# Sheet1.net
KiCad netlist of a schematic drawn in Altium Designer
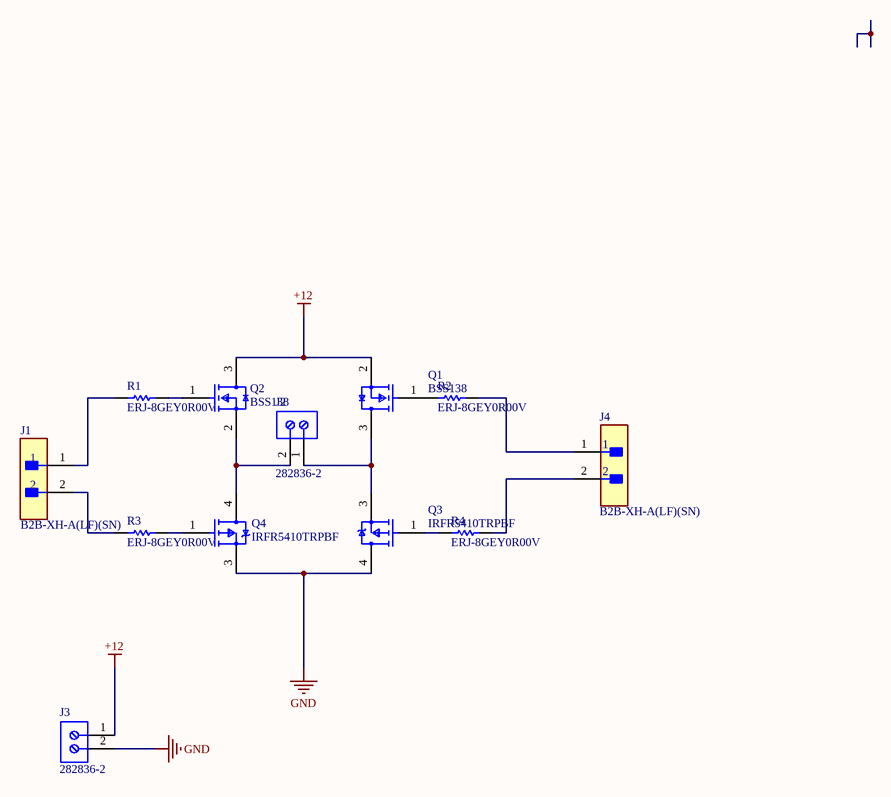
[diagram p0: Sheet1.SchDoc]

(export (version "E")
  (design (tool "Eeschema 10.0.6"))
  (components
    (comp (ref "J1")
      (value "B2B-XH-A(LF)(SN)")
      (footprint "FP-B2B-XH-A_LF_SN-MFG")
      (description "CONN HEADER VERT 2POS 2.5MM")
      (libsource (lib "") (part "3bc925449376181038e59eaffc5286c_1"))
    )
    (comp (ref "J2")
      (value "282836-2")
      (footprint "TECO-282836-2_V")
      (description "Female Header, Pitch 5 mm, 1 x 2 Position, Height 10 mm, Tail Length 3.5 mm, Rohs, Bulk")
      (fields (field (name "VOLTAGE") "300V") (field (name "MANUFACTURER") "TE Connectivity"))
      (libsource (lib "Altium Content Vault") (part "CN-1P-F-TB2"))
    )
    (comp (ref "J3")
      (value "282836-2")
      (footprint "TECO-282836-2_V")
      (description "Female Header, Pitch 5 mm, 1 x 2 Position, Height 10 mm, Tail Length 3.5 mm, Rohs, Bulk")
      (fields (field (name "VOLTAGE") "300V") (field (name "MANUFACTURER") "TE Connectivity"))
      (libsource (lib "Altium Content Vault") (part "CN-1P-F-TB2"))
    )
    (comp (ref "J4")
      (value "B2B-XH-A(LF)(SN)")
      (footprint "FP-B2B-XH-A_LF_SN-MFG")
      (description "CONN HEADER VERT 2POS 2.5MM")
      (libsource (lib "Altium Content Vault") (part "3bc925449376181038e59eaffc5286c"))
    )
    (comp (ref "Q1")
      (value "BSS138")
      (footprint "FP-318-08-IPC_B")
      (description "MOSFET N-CH 50V 220MA SOT-23")
      (libsource (lib "Altium Content Vault") (part "3b9c635fedb024a5347a57b145af9cc"))
    )
    (comp (ref "Q2")
      (value "BSS138")
      (footprint "FP-318-08-IPC_B")
      (description "MOSFET N-CH 50V 220MA SOT-23")
      (libsource (lib "Altium Content Vault") (part "3b9c635fedb024a5347a57b145af9cc"))
    )
    (comp (ref "Q3")
      (value "IRFR5410TRPBF")
      (footprint "FP-PG-TO252-3-MFG")
      (description "MOSFET P-CH 100V 13A DPAK")
      (fields
        (field (name "MANUFACTURER") "Infineon")
        (field (name "OCTOPART") "https://octopart.com/irfr5410trpbf-infineon-65874169")
      )
      (libsource (lib "Altium Content Vault") (part "84bd51c0c313388725e75e773aba525"))
    )
    (comp (ref "Q4")
      (value "IRFR5410TRPBF")
      (footprint "FP-PG-TO252-3-MFG")
      (description "MOSFET P-CH 100V 13A DPAK")
      (fields
        (field (name "MANUFACTURER") "Infineon")
        (field (name "OCTOPART") "https://octopart.com/irfr5410trpbf-infineon-65874169")
      )
      (libsource (lib "Altium Content Vault") (part "84bd51c0c313388725e75e773aba525"))
    )
    (comp (ref "R1")
      (value "ERJ-8GEY0R00V")
      (footprint "RESC3216X70X50NL05T20")
      (fields (field (name "MANUFACTURER") "Panasonic"))
      (libsource (lib "Altium Content Vault") (part "RES"))
    )
    (comp (ref "R2")
      (value "ERJ-8GEY0R00V")
      (footprint "RESC3216X70X50NL05T20")
      (fields (field (name "MANUFACTURER") "Panasonic"))
      (libsource (lib "Altium Content Vault") (part "RES"))
    )
    (comp (ref "R3")
      (value "ERJ-8GEY0R00V")
      (footprint "RESC3216X70X50NL05T20")
      (fields (field (name "MANUFACTURER") "Panasonic"))
      (libsource (lib "Altium Content Vault") (part "RES"))
    )
    (comp (ref "R4")
      (value "ERJ-8GEY0R00V")
      (footprint "RESC3216X70X50NL05T20")
      (fields (field (name "MANUFACTURER") "Panasonic"))
      (libsource (lib "Altium Content Vault") (part "RES"))
    )
  )
  (nets
    (net (code "1") (name "+12") (class "Default")
      (node (ref "J3") (pin "1") (pinfunction "1_1") (pintype "passive"))
      (node (ref "Q1") (pin "2") (pinfunction "S_2") (pintype "passive"))
      (node (ref "Q2") (pin "3") (pinfunction "D_3") (pintype "passive"))
    )
    (net (code "2") (name "GND") (class "Default")
      (node (ref "J3") (pin "2") (pinfunction "2_2") (pintype "passive"))
      (node (ref "Q3") (pin "4") (pinfunction "D_4") (pintype "passive"))
      (node (ref "Q4") (pin "3") (pinfunction "S_3") (pintype "passive"))
    )
    (net (code "3") (name "Net-(J1-Pad1)") (class "Default")
      (node (ref "J1") (pin "1") (pinfunction "1_1") (pintype "passive"))
      (node (ref "R1") (pin "1") (pinfunction "1_1") (pintype "passive"))
    )
    (net (code "4") (name "Net-(J1-Pad2)") (class "Default")
      (node (ref "J1") (pin "2") (pinfunction "2_2") (pintype "passive"))
      (node (ref "R3") (pin "1") (pinfunction "1_1") (pintype "passive"))
    )
    (net (code "5") (name "Net-(J4-Pad1)") (class "Default")
      (node (ref "J4") (pin "1") (pinfunction "1_1") (pintype "passive"))
      (node (ref "R2") (pin "2") (pinfunction "2_2") (pintype "passive"))
    )
    (net (code "6") (name "Net-(J4-Pad2)") (class "Default")
      (node (ref "J4") (pin "2") (pinfunction "2_2") (pintype "passive"))
      (node (ref "R4") (pin "2") (pinfunction "2_2") (pintype "passive"))
    )
    (net (code "7") (name "Net-(Q1-D)") (class "Default")
      (node (ref "J2") (pin "1") (pinfunction "1_1") (pintype "passive"))
      (node (ref "Q1") (pin "3") (pinfunction "D_3") (pintype "passive"))
      (node (ref "Q3") (pin "3") (pinfunction "S_3") (pintype "passive"))
    )
    (net (code "8") (name "Net-(Q1-G)") (class "Default")
      (node (ref "Q1") (pin "1") (pinfunction "G_1") (pintype "passive"))
      (node (ref "R2") (pin "1") (pinfunction "1_1") (pintype "passive"))
    )
    (net (code "9") (name "Net-(Q2-G)") (class "Default")
      (node (ref "Q2") (pin "1") (pinfunction "G_1") (pintype "passive"))
      (node (ref "R1") (pin "2") (pinfunction "2_2") (pintype "passive"))
    )
    (net (code "10") (name "Net-(Q2-S)") (class "Default")
      (node (ref "J2") (pin "2") (pinfunction "2_2") (pintype "passive"))
      (node (ref "Q2") (pin "2") (pinfunction "S_2") (pintype "passive"))
      (node (ref "Q4") (pin "4") (pinfunction "D_4") (pintype "passive"))
    )
    (net (code "11") (name "Net-(Q3-G)") (class "Default")
      (node (ref "Q3") (pin "1") (pinfunction "G_1") (pintype "passive"))
      (node (ref "R4") (pin "1") (pinfunction "1_1") (pintype "passive"))
    )
    (net (code "12") (name "Net-(Q4-G)") (class "Default")
      (node (ref "Q4") (pin "1") (pinfunction "G_1") (pintype "passive"))
      (node (ref "R3") (pin "2") (pinfunction "2_2") (pintype "passive"))
    )
  )
)
